# Stepper_motor_driver.net
KiCad netlist of a schematic drawn in Altium Designer
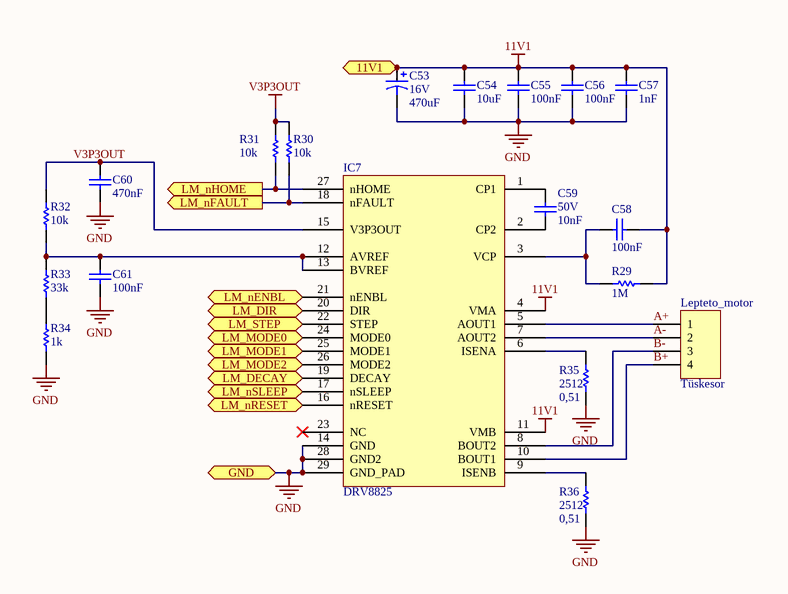
[diagram p0: Stepper_motor_driver.SchDoc]

(export (version "E")
  (design (tool "Eeschema 10.0.6"))
  (components
    (comp (ref "C53")
      (value "16V")
      (footprint "power_cap_10mm")
      (description "Polarized Capacitor (Radial)")
      (fields (field (name "ALTIUM_VALUE") "470uF") (field (name "PUBLISHER") "Altium Limited"))
      (libsource (lib "Miscellaneous Devices") (part "Cap Pol1"))
    )
    (comp (ref "C54")
      (value "10uF")
      (footprint "FP_1206_CAP_125")
      (description "Capacitor")
      (fields (field (name "Comment") "50V") (field (name "PUBLISHER") "Altium Limited"))
      (libsource (lib "Miscellaneous Devices") (part "Cap"))
    )
    (comp (ref "C55")
      (value "100nF")
      (footprint "FP_0603_CAP_080")
      (description "Capacitor")
      (fields (field (name "Comment") "50V") (field (name "PUBLISHER") "Altium Limited"))
      (libsource (lib "Miscellaneous Devices") (part "Cap"))
    )
    (comp (ref "C56")
      (value "100nF")
      (footprint "FP_0603_CAP_080")
      (description "Capacitor")
      (fields (field (name "Comment") "50V") (field (name "PUBLISHER") "Altium Limited"))
      (libsource (lib "Miscellaneous Devices") (part "Cap"))
    )
    (comp (ref "C57")
      (value "1nF")
      (footprint "FP_0603_CAP_080")
      (description "Capacitor")
      (fields (field (name "Comment") "50V") (field (name "PUBLISHER") "Altium Limited"))
      (libsource (lib "Miscellaneous Devices") (part "Cap"))
    )
    (comp (ref "C58")
      (value "100nF")
      (footprint "FP_0603_CAP_080")
      (description "Capacitor")
      (fields (field (name "Comment") "16V") (field (name "PUBLISHER") "Altium Limited"))
      (libsource (lib "Miscellaneous Devices") (part "Cap"))
    )
    (comp (ref "C59")
      (value "50V")
      (footprint "FP_0603_CAP_080")
      (description "Capacitor")
      (fields (field (name "ALTIUM_VALUE") "10nF") (field (name "PUBLISHER") "Altium Limited"))
      (libsource (lib "Miscellaneous Devices") (part "Cap"))
    )
    (comp (ref "C60")
      (value "470nF")
      (footprint "FP_0603_CAP_080")
      (description "Capacitor")
      (fields (field (name "Comment") "50V") (field (name "PUBLISHER") "Altium Limited"))
      (libsource (lib "Miscellaneous Devices") (part "Cap"))
    )
    (comp (ref "C61")
      (value "100nF")
      (footprint "FP_0603_CAP_080")
      (description "Capacitor")
      (fields (field (name "Comment") "50V") (field (name "PUBLISHER") "Altium Limited"))
      (libsource (lib "Miscellaneous Devices") (part "Cap"))
    )
    (comp (ref "IC7")
      (value "DRV8825")
      (footprint "TSSOP28_thermal_pad")
      (libsource (lib "diploma") (part "DRV8825"))
    )
    (comp (ref "Lepteto_motor")
      (value "Tüskesor")
      (footprint "FP_CONN4_TUSKE_254MM")
      (description "Header, 4-Pin")
      (fields (field (name "PUBLISHER") "Altium Limited"))
      (libsource (lib "Miscellaneous Connectors") (part "Header 4"))
    )
    (comp (ref "R29")
      (value "1M")
      (footprint "FP_0603_RES")
      (description "Semiconductor Resistor")
      (fields (field (name "Comment") "Res1") (field (name "PUBLISHER") "Altium Limited"))
      (libsource (lib "Miscellaneous Devices") (part "Res Semi"))
    )
    (comp (ref "R30")
      (value "10k")
      (footprint "FP_0603_RES")
      (description "Semiconductor Resistor")
      (fields (field (name "Comment") "Res Semi") (field (name "PUBLISHER") "Altium Limited"))
      (libsource (lib "Miscellaneous Devices") (part "Res Semi"))
    )
    (comp (ref "R31")
      (value "10k")
      (footprint "FP_0603_RES")
      (description "Semiconductor Resistor")
      (fields (field (name "Comment") "Res Semi") (field (name "PUBLISHER") "Altium Limited"))
      (libsource (lib "Miscellaneous Devices") (part "Res Semi"))
    )
    (comp (ref "R32")
      (value "10k")
      (footprint "FP_0603_RES")
      (description "Semiconductor Resistor")
      (fields (field (name "Comment") "Res Semi") (field (name "PUBLISHER") "Altium Limited"))
      (libsource (lib "Miscellaneous Devices") (part "Res Semi"))
    )
    (comp (ref "R33")
      (value "33k")
      (footprint "FP_0603_RES")
      (description "Semiconductor Resistor")
      (fields (field (name "Comment") "Res Semi") (field (name "PUBLISHER") "Altium Limited"))
      (libsource (lib "Miscellaneous Devices") (part "Res Semi"))
    )
    (comp (ref "R34")
      (value "1k")
      (footprint "FP_0603_RES")
      (description "Semiconductor Resistor")
      (fields (field (name "Comment") "Res Semi") (field (name "PUBLISHER") "Altium Limited"))
      (libsource (lib "Miscellaneous Devices") (part "Res Semi"))
    )
    (comp (ref "R35")
      (value "2512")
      (footprint "RES_2512")
      (description "Semiconductor Resistor")
      (fields (field (name "ALTIUM_VALUE") "0,51") (field (name "PUBLISHER") "Altium Limited"))
      (libsource (lib "Miscellaneous Devices") (part "Res Semi"))
    )
    (comp (ref "R36")
      (value "2512")
      (footprint "RES_2512")
      (description "Semiconductor Resistor")
      (fields (field (name "ALTIUM_VALUE") "0,51") (field (name "PUBLISHER") "Altium Limited"))
      (libsource (lib "Miscellaneous Devices") (part "Res Semi"))
    )
  )
  (nets
    (net (code "1") (name "/A+") (class "Default")
      (node (ref "IC7") (pin "5") (pinfunction "AOUT1_5") (pintype "passive"))
      (node (ref "Lepteto_motor") (pin "1") (pinfunction "1_1") (pintype "passive"))
    )
    (net (code "2") (name "/A-") (class "Default")
      (node (ref "IC7") (pin "7") (pinfunction "AOUT2_7") (pintype "passive"))
      (node (ref "Lepteto_motor") (pin "2") (pinfunction "2_2") (pintype "passive"))
    )
    (net (code "3") (name "/B+") (class "Default")
      (node (ref "IC7") (pin "10") (pinfunction "BOUT1_10") (pintype "passive"))
      (node (ref "Lepteto_motor") (pin "4") (pinfunction "4_4") (pintype "passive"))
    )
    (net (code "4") (name "/B-") (class "Default")
      (node (ref "IC7") (pin "8") (pinfunction "BOUT2_8") (pintype "passive"))
      (node (ref "Lepteto_motor") (pin "3") (pinfunction "3_3") (pintype "passive"))
    )
    (net (code "5") (name "/LM_DECAY") (class "Default")
      (node (ref "IC7") (pin "19") (pinfunction "DECAY_19") (pintype "passive"))
    )
    (net (code "6") (name "/LM_DIR") (class "Default")
      (node (ref "IC7") (pin "20") (pinfunction "DIR_20") (pintype "passive"))
    )
    (net (code "7") (name "/LM_MODE0") (class "Default")
      (node (ref "IC7") (pin "24") (pinfunction "MODE0_24") (pintype "passive"))
    )
    (net (code "8") (name "/LM_MODE1") (class "Default")
      (node (ref "IC7") (pin "25") (pinfunction "MODE1_25") (pintype "passive"))
    )
    (net (code "9") (name "/LM_MODE2") (class "Default")
      (node (ref "IC7") (pin "26") (pinfunction "MODE2_26") (pintype "passive"))
    )
    (net (code "10") (name "/LM_STEP") (class "Default")
      (node (ref "IC7") (pin "22") (pinfunction "STEP_22") (pintype "passive"))
    )
    (net (code "11") (name "/LM_nENBL") (class "Default")
      (node (ref "IC7") (pin "21") (pinfunction "nENBL_21") (pintype "passive"))
    )
    (net (code "12") (name "/LM_nFAULT") (class "Default")
      (node (ref "IC7") (pin "18") (pinfunction "nFAULT_18") (pintype "passive"))
      (node (ref "R30") (pin "1") (pinfunction "1_1") (pintype "passive"))
    )
    (net (code "13") (name "/LM_nHOME") (class "Default")
      (node (ref "IC7") (pin "27") (pinfunction "nHOME_27") (pintype "passive"))
      (node (ref "R31") (pin "1") (pinfunction "1_1") (pintype "passive"))
    )
    (net (code "14") (name "/LM_nRESET") (class "Default")
      (node (ref "IC7") (pin "16") (pinfunction "nRESET_16") (pintype "passive"))
    )
    (net (code "15") (name "/LM_nSLEEP") (class "Default")
      (node (ref "IC7") (pin "17") (pinfunction "nSLEEP_17") (pintype "passive"))
    )
    (net (code "16") (name "11V1") (class "Default")
      (node (ref "C53") (pin "1") (pinfunction "1_1") (pintype "passive"))
      (node (ref "C54") (pin "2") (pinfunction "2_2") (pintype "passive"))
      (node (ref "C55") (pin "2") (pinfunction "2_2") (pintype "passive"))
      (node (ref "C56") (pin "2") (pinfunction "2_2") (pintype "passive"))
      (node (ref "C57") (pin "1") (pinfunction "1_1") (pintype "passive"))
      (node (ref "C58") (pin "2") (pinfunction "2_2") (pintype "passive"))
      (node (ref "IC7") (pin "11") (pinfunction "VMB_11") (pintype "passive"))
      (node (ref "IC7") (pin "4") (pinfunction "VMA_4") (pintype "passive"))
      (node (ref "R29") (pin "1") (pinfunction "1_1") (pintype "passive"))
    )
    (net (code "17") (name "GND") (class "Default")
      (node (ref "C53") (pin "2") (pinfunction "2_2") (pintype "passive"))
      (node (ref "C54") (pin "1") (pinfunction "1_1") (pintype "passive"))
      (node (ref "C55") (pin "1") (pinfunction "1_1") (pintype "passive"))
      (node (ref "C56") (pin "1") (pinfunction "1_1") (pintype "passive"))
      (node (ref "C57") (pin "2") (pinfunction "2_2") (pintype "passive"))
      (node (ref "C60") (pin "1") (pinfunction "1_1") (pintype "passive"))
      (node (ref "C61") (pin "1") (pinfunction "1_1") (pintype "passive"))
      (node (ref "IC7") (pin "14") (pinfunction "GND_14") (pintype "passive"))
      (node (ref "IC7") (pin "28") (pinfunction "GND2_28") (pintype "passive"))
      (node (ref "IC7") (pin "29") (pinfunction "GND_PAD_29") (pintype "passive"))
      (node (ref "R34") (pin "1") (pinfunction "1_1") (pintype "passive"))
      (node (ref "R35") (pin "1") (pinfunction "1_1") (pintype "passive"))
      (node (ref "R36") (pin "1") (pinfunction "1_1") (pintype "passive"))
    )
    (net (code "18") (name "Net-(IC7-AVREF)") (class "Default")
      (node (ref "C61") (pin "2") (pinfunction "2_2") (pintype "passive"))
      (node (ref "IC7") (pin "12") (pinfunction "AVREF_12") (pintype "passive"))
      (node (ref "IC7") (pin "13") (pinfunction "BVREF_13") (pintype "passive"))
      (node (ref "R32") (pin "1") (pinfunction "1_1") (pintype "passive"))
      (node (ref "R33") (pin "2") (pinfunction "2_2") (pintype "passive"))
    )
    (net (code "19") (name "Net-(IC7-CP1)") (class "Default")
      (node (ref "C59") (pin "2") (pinfunction "2_2") (pintype "passive"))
      (node (ref "IC7") (pin "1") (pinfunction "CP1_1") (pintype "passive"))
    )
    (net (code "20") (name "Net-(IC7-CP2)") (class "Default")
      (node (ref "C59") (pin "1") (pinfunction "1_1") (pintype "passive"))
      (node (ref "IC7") (pin "2") (pinfunction "CP2_2") (pintype "passive"))
    )
    (net (code "21") (name "Net-(IC7-ISENA)") (class "Default")
      (node (ref "IC7") (pin "6") (pinfunction "ISENA_6") (pintype "passive"))
      (node (ref "R35") (pin "2") (pinfunction "2_2") (pintype "passive"))
    )
    (net (code "22") (name "Net-(IC7-ISENB)") (class "Default")
      (node (ref "IC7") (pin "9") (pinfunction "ISENB_9") (pintype "passive"))
      (node (ref "R36") (pin "2") (pinfunction "2_2") (pintype "passive"))
    )
    (net (code "23") (name "Net-(IC7-VCP)") (class "Default")
      (node (ref "C58") (pin "1") (pinfunction "1_1") (pintype "passive"))
      (node (ref "IC7") (pin "3") (pinfunction "VCP_3") (pintype "passive"))
      (node (ref "R29") (pin "2") (pinfunction "2_2") (pintype "passive"))
    )
    (net (code "24") (name "Net-(R33-Pad1)") (class "Default")
      (node (ref "R33") (pin "1") (pinfunction "1_1") (pintype "passive"))
      (node (ref "R34") (pin "2") (pinfunction "2_2") (pintype "passive"))
    )
    (net (code "25") (name "V3P3OUT") (class "Default")
      (node (ref "C60") (pin "2") (pinfunction "2_2") (pintype "passive"))
      (node (ref "IC7") (pin "15") (pinfunction "V3P3OUT_15") (pintype "passive"))
      (node (ref "R30") (pin "2") (pinfunction "2_2") (pintype "passive"))
      (node (ref "R31") (pin "2") (pinfunction "2_2") (pintype "passive"))
      (node (ref "R32") (pin "2") (pinfunction "2_2") (pintype "passive"))
    )
    (net (code "26") (name "unconnected-(IC7-NC-Pad23)") (class "Default")
      (node (ref "IC7") (pin "23") (pinfunction "NC_23") (pintype "passive+no_connect"))
    )
  )
)
